# H18R1_Frontend_1.net
KiCad netlist of a schematic drawn in Altium Designer
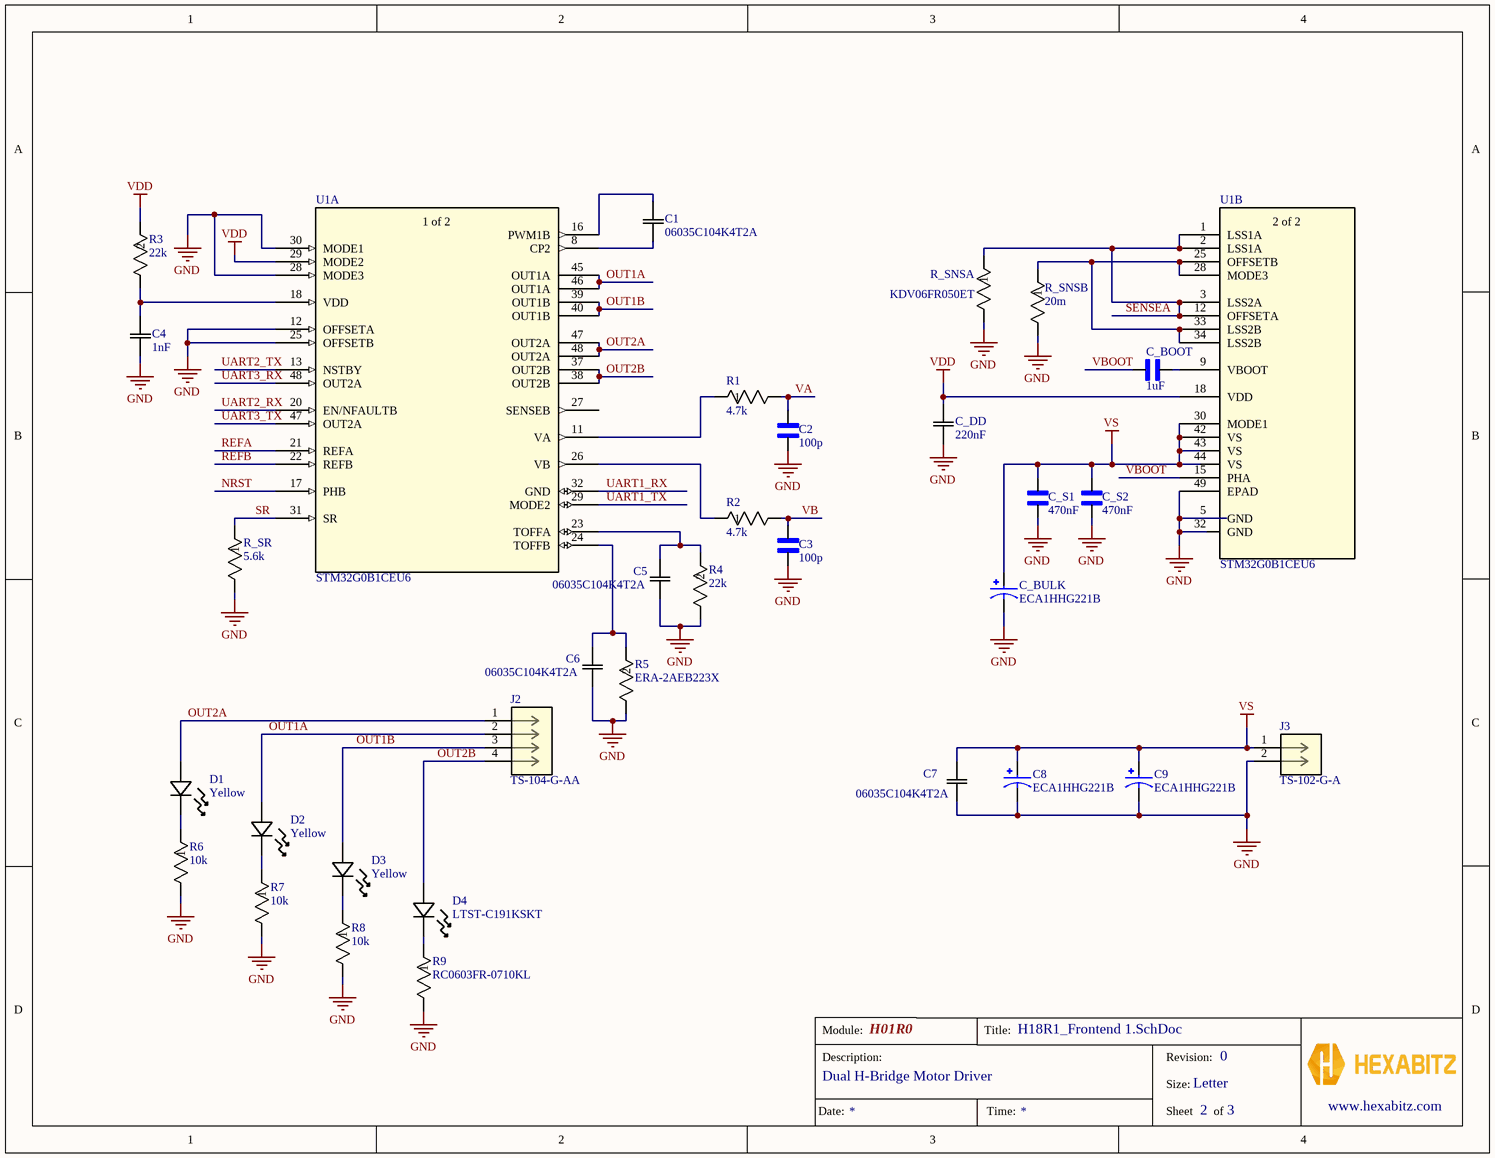
[diagram p0: H18R1_Frontend 1.SchDoc]

(export (version "E")
  (design (tool "Eeschema 10.0.6"))
  (components
    (comp (ref "C1")
      (value "06035C104K4T2A")
      (footprint "CAP_0603_AVX")
      (description "Description")
      (fields (field (name "COPYRIGHT") "Copyright (C) 2025 Ultra Librarian. All rights reserved."))
      (libsource (lib "H18R1") (part "06035C104K4T2A"))
    )
    (comp (ref "C2")
      (value "100p")
      (footprint "CAPC1005X55N")
      (description "100 pF Â±5% 50V Ceramic Capacitor C0G, NP0 0402 (1005 Metric)")
      (fields (field (name "MF") "Yageo") (field (name "MP") "CC0402JRNPO9BN101"))
      (libsource (lib "H18R1") (part "CC0402JRNPO9BN101"))
    )
    (comp (ref "C3")
      (value "100p")
      (footprint "CAPC1005X55N")
      (description "100 pF Â±5% 50V Ceramic Capacitor C0G, NP0 0402 (1005 Metric)")
      (fields (field (name "MF") "Yageo") (field (name "MP") "CC0402JRNPO9BN101"))
      (libsource (lib "H18R1") (part "CC0402JRNPO9BN101"))
    )
    (comp (ref "C4")
      (value "1nF")
      (footprint "CAPC17595_87N_KEM")
      (description "SMD Comm X7R, Ceramic, 1000 pF, 10%, 50 VDC, X7R, SMD, MLCC, Temperature Stable, Class II, 0603")
      (fields
        (field (name "MANUFACTURER_PART_NUMBER") "C0603C102K5RACTU")
        (field (name "COPYRIGHT") "Copyright (C) 2025 Ultra Librarian. All rights reserved.")
      )
      (libsource (lib "H18R1") (part "C0603C102K5RACTU"))
    )
    (comp (ref "C5")
      (value "06035C104K4T2A")
      (footprint "CAP_0603_AVX")
      (description "Description")
      (fields (field (name "COPYRIGHT") "Copyright (C) 2025 Ultra Librarian. All rights reserved."))
      (libsource (lib "H18R1") (part "06035C104K4T2A"))
    )
    (comp (ref "C6")
      (value "06035C104K4T2A")
      (footprint "CAP_0603_AVX")
      (description "Description")
      (fields (field (name "COPYRIGHT") "Copyright (C) 2025 Ultra Librarian. All rights reserved."))
      (libsource (lib "H18R1") (part "06035C104K4T2A"))
    )
    (comp (ref "C7")
      (value "06035C104K4T2A")
      (footprint "CAP_0603_AVX")
      (description "Description")
      (fields (field (name "COPYRIGHT") "Copyright (C) 2025 Ultra Librarian. All rights reserved."))
      (libsource (lib "H18R1") (part "06035C104K4T2A"))
    )
    (comp (ref "C8")
      (value "ECA1HHG221B")
      (footprint "CAPPRD500W60D1000H1250:CAPPRD500W60D1000H1250")
      (description "Cap Aluminum Lytic 220uF 50V 20% (10 X 12.5mm) Radial 5mm 300mA 2000h 105??? Ammo Pack")
      (fields (field (name "MF") "Panasonic Electronic") (field (name "MP") "ECA-1HHG221B"))
      (libsource (lib "H18R1") (part "ECA1HHG221B"))
    )
    (comp (ref "C9")
      (value "ECA1HHG221B")
      (footprint "CAPPRD500W60D1000H1250:CAPPRD500W60D1000H1250")
      (description "Cap Aluminum Lytic 220uF 50V 20% (10 X 12.5mm) Radial 5mm 300mA 2000h 105??? Ammo Pack")
      (fields (field (name "MF") "Panasonic Electronic") (field (name "MP") "ECA-1HHG221B"))
      (libsource (lib "ECA1HHG221B") (part "ECA1HHG221B"))
    )
    (comp (ref "C_BOOT")
      (value "1uF")
      (footprint "CAPC2012X135N")
      (description "1 ÂµF Â±10% 50V Ceramic Capacitor X7R 0805 (2012 Metric)")
      (fields (field (name "MF") "Samsung") (field (name "MP") "CL21B105KBFNNNE"))
      (libsource (lib "H18R1") (part "CL21B105KBFNNNE"))
    )
    (comp (ref "C_BULK")
      (value "ECA1HHG221B")
      (footprint "CAPPRD500W60D1000H1250:CAPPRD500W60D1000H1250")
      (description "Cap Aluminum Lytic 220uF 50V 20% (10 X 12.5mm) Radial 5mm 300mA 2000h 105??? Ammo Pack")
      (fields (field (name "MF") "Panasonic Electronic") (field (name "MP") "ECA-1HHG221B"))
      (libsource (lib "ECA1HHG221B") (part "ECA1HHG221B"))
    )
    (comp (ref "C_DD")
      (value "220nF")
      (footprint "cap_UMK105 CG080CV-F_TAY")
      (description "Description")
      (fields
        (field (name "MANUFACTURER_PART_NUMBER") "UMK105BJ224KV-F")
        (field (name "COPYRIGHT") "Copyright (C) 2025 Ultra Librarian. All rights reserved.")
      )
      (libsource (lib "H18R1") (part "UMK105BJ224KV-F"))
    )
    (comp (ref "C_S1")
      (value "470nF")
      (footprint "CAPC1005X60N")
      (description "SMD capacitor X5R(EIA) with capacitance 0.47uF Tol.10%. Rated voltage 50Vdc 85C")
      (fields (field (name "MF") "Murata Electronics") (field (name "MP") "GRM155R61H474KE11D"))
      (libsource (lib "H18R1") (part "GRM155R61H474KE11D"))
    )
    (comp (ref "C_S2")
      (value "470nF")
      (footprint "CAPC1005X60N")
      (description "SMD capacitor X5R(EIA) with capacitance 0.47uF Tol.10%. Rated voltage 50Vdc 85C")
      (fields (field (name "MF") "Murata Electronics") (field (name "MP") "GRM155R61H474KE11D"))
      (libsource (lib "H18R1") (part "GRM155R61H474KE11D"))
    )
    (comp (ref "D1")
      (value "Yellow")
      (footprint "LED_LTST-C191KRKT_LTO")
      (description "Description")
      (fields
        (field (name "MANUFACTURER_PART_NUMBER") "LTST-C191KSKT")
        (field (name "COPYRIGHT") "Copyright (C) 2025 Ultra Librarian. All rights reserved.")
      )
      (libsource (lib "H18R1") (part "LTST-C191KSKT"))
    )
    (comp (ref "D2")
      (value "Yellow")
      (footprint "LED_LTST-C191KRKT_LTO")
      (description "Description")
      (fields
        (field (name "MANUFACTURER_PART_NUMBER") "LTST-C191KSKT")
        (field (name "COPYRIGHT") "Copyright (C) 2025 Ultra Librarian. All rights reserved.")
      )
      (libsource (lib "H18R1") (part "LTST-C191KSKT"))
    )
    (comp (ref "D3")
      (value "Yellow")
      (footprint "LED_LTST-C191KRKT_LTO")
      (description "Description")
      (fields
        (field (name "MANUFACTURER_PART_NUMBER") "LTST-C191KSKT")
        (field (name "COPYRIGHT") "Copyright (C) 2025 Ultra Librarian. All rights reserved.")
      )
      (libsource (lib "H18R1") (part "LTST-C191KSKT"))
    )
    (comp (ref "D4")
      (value "LTST-C191KSKT")
      (footprint "LED_LTST-C191KRKT_LTO")
      (description "Description")
      (fields (field (name "COPYRIGHT") "Copyright (C) 2025 Ultra Librarian. All rights reserved."))
      (libsource (lib "H18R1") (part "LTST-C191KSKT"))
    )
    (comp (ref "J2")
      (value "TS-104-G-AA")
      (footprint "CON4_1X4_TU_HTS_SAI")
      (description "Description")
      (fields (field (name "COPYRIGHT") "Copyright (C) 2025 Ultra Librarian. All rights reserved."))
      (libsource (lib "H18R1") (part "TS-104-G-AA"))
    )
    (comp (ref "J3")
      (value "TS-102-G-A")
      (footprint "CON2_1X2_TU_HTS_SAI")
      (description "Description")
      (fields (field (name "COPYRIGHT") "Copyright (C) 2025 Ultra Librarian. All rights reserved."))
      (libsource (lib "H18R1") (part "TS-102-G-A"))
    )
    (comp (ref "R1")
      (value "4.7k")
      (footprint "YAG_R0402_YAG")
      (description "Description")
      (fields
        (field (name "MANUFACTURER_PART_NUMBER") "RC0402FR-074K7L")
        (field (name "COPYRIGHT") "Copyright (C) 2025 Ultra Librarian. All rights reserved.")
      )
      (libsource (lib "H18R1") (part "RC0402FR-074K7L"))
    )
    (comp (ref "R2")
      (value "4.7k")
      (footprint "YAG_R0402_YAG")
      (description "Description")
      (fields
        (field (name "MANUFACTURER_PART_NUMBER") "RC0402FR-074K7L")
        (field (name "COPYRIGHT") "Copyright (C) 2025 Ultra Librarian. All rights reserved.")
      )
      (libsource (lib "H18R1") (part "RC0402FR-074K7L"))
    )
    (comp (ref "R3")
      (value "22k")
      (footprint "RC0402N_PAN")
      (description "Description")
      (fields
        (field (name "MANUFACTURER_PART_NUMBER") "ERA-2AEB223X")
        (field (name "COPYRIGHT") "Copyright (C) 2025 Ultra Librarian. All rights reserved.")
      )
      (libsource (lib "H18R1") (part "ERA-2AEB223X"))
    )
    (comp (ref "R4")
      (value "22k")
      (footprint "RC0402N_PAN")
      (description "Description")
      (fields
        (field (name "MANUFACTURER_PART_NUMBER") "ERA-2AEB223X")
        (field (name "COPYRIGHT") "Copyright (C) 2025 Ultra Librarian. All rights reserved.")
      )
      (libsource (lib "H18R1") (part "ERA-2AEB223X"))
    )
    (comp (ref "R5")
      (value "ERA-2AEB223X")
      (footprint "RC0402N_PAN")
      (description "Description")
      (fields (field (name "COPYRIGHT") "Copyright (C) 2025 Ultra Librarian. All rights reserved."))
      (libsource (lib "H18R1") (part "ERA-2AEB223X"))
    )
    (comp (ref "R6")
      (value "10k")
      (footprint "RC0603N_YAG")
      (description "RES SMD 10kO 1% 1/10W 0603")
      (fields
        (field (name "MANUFACTURER_PART_NUMBER") "RC0603FR-0710KL")
        (field (name "COPYRIGHT") "Copyright (C) 2025 Ultra Librarian. All rights reserved.")
      )
      (libsource (lib "H18R1") (part "RC0603FR-0710KL"))
    )
    (comp (ref "R7")
      (value "10k")
      (footprint "RC0603N_YAG")
      (description "RES SMD 10kO 1% 1/10W 0603")
      (fields
        (field (name "MANUFACTURER_PART_NUMBER") "RC0603FR-0710KL")
        (field (name "COPYRIGHT") "Copyright (C) 2025 Ultra Librarian. All rights reserved.")
      )
      (libsource (lib "H18R1") (part "RC0603FR-0710KL"))
    )
    (comp (ref "R8")
      (value "10k")
      (footprint "RC0603N_YAG")
      (description "RES SMD 10kO 1% 1/10W 0603")
      (fields
        (field (name "MANUFACTURER_PART_NUMBER") "RC0603FR-0710KL")
        (field (name "COPYRIGHT") "Copyright (C) 2025 Ultra Librarian. All rights reserved.")
      )
      (libsource (lib "H18R1") (part "RC0603FR-0710KL"))
    )
    (comp (ref "R9")
      (value "RC0603FR-0710KL")
      (footprint "RC0603N_YAG")
      (description "RES SMD 10kO 1% 1/10W 0603")
      (fields (field (name "COPYRIGHT") "Copyright (C) 2025 Ultra Librarian. All rights reserved."))
      (libsource (lib "H18R1") (part "RC0603FR-0710KL"))
    )
    (comp (ref "R_SNSA")
      (value "KDV06FR050ET")
      (footprint "RES_KDV06_OHM")
      (description "Description")
      (fields (field (name "COPYRIGHT") "Copyright (C) 2025 Ultra Librarian. All rights reserved."))
      (libsource (lib "H18R1") (part "KDV06FR050ET"))
    )
    (comp (ref "R_SNSB")
      (value "20m")
      (footprint "RES_KDV06_OHM")
      (description "Description")
      (fields
        (field (name "MANUFACTURER_PART_NUMBER") "KDV06FR050ET")
        (field (name "COPYRIGHT") "Copyright (C) 2025 Ultra Librarian. All rights reserved.")
      )
      (libsource (lib "H18R1") (part "KDV06FR050ET"))
    )
    (comp (ref "R_SR")
      (value "5.6k")
      (footprint "YAG_R0402_YAG")
      (description "No Description Available")
      (fields
        (field (name "MANUFACTURER_PART_NUMBER") "RC0402FR-075K6L")
        (field (name "COPYRIGHT") "Copyright (C) 2025 Ultra Librarian. All rights reserved.")
      )
      (libsource (lib "H18R1") (part "RC0402FR-075K6L"))
    )
    (comp (ref "U1")
      (value "STM32G0B1CEU6")
      (footprint "QFN50P700X700X65-49N-D")
      (description "Scalable 4.5 A dual full-bridge driver for brushed DC motors")
      (fields
        (field (name "MANUFACTURER_PART_NUMBER") "STSPIN948")
        (field (name "COPYRIGHT") "Copyright (C) 2025 Ultra Librarian. All rights reserved.")
      )
      (libsource (lib "") (part "STSPIN948_1"))
    )
  )
  (nets
    (net (code "1") (name "/NRST") (class "Default")
      (node (ref "U1") (pin "17") (pinfunction "PHB_17") (pintype "input"))
    )
    (net (code "2") (name "/OUT1A") (class "Default")
      (node (ref "D2") (pin "2") (pinfunction "2_2") (pintype "passive"))
      (node (ref "J2") (pin "2") (pinfunction "2_2") (pintype "passive"))
      (node (ref "U1") (pin "45") (pinfunction "OUT1A_45") (pintype "power_in"))
      (node (ref "U1") (pin "46") (pinfunction "OUT1A_46") (pintype "power_in"))
    )
    (net (code "3") (name "/OUT1B") (class "Default")
      (node (ref "D3") (pin "2") (pinfunction "2_2") (pintype "passive"))
      (node (ref "J2") (pin "3") (pinfunction "3_3") (pintype "passive"))
      (node (ref "U1") (pin "39") (pinfunction "OUT1B_39") (pintype "power_in"))
      (node (ref "U1") (pin "40") (pinfunction "OUT1B_40") (pintype "power_in"))
    )
    (net (code "4") (name "/OUT2A") (class "Default")
      (node (ref "D1") (pin "2") (pinfunction "2_2") (pintype "passive"))
      (node (ref "J2") (pin "1") (pinfunction "1_1") (pintype "passive"))
      (node (ref "U1") (pin "47") (pinfunction "OUT2A_47") (pintype "power_in"))
      (node (ref "U1") (pin "48") (pinfunction "OUT2A_48") (pintype "power_in"))
    )
    (net (code "5") (name "/OUT2B") (class "Default")
      (node (ref "D4") (pin "2") (pinfunction "2_2") (pintype "passive"))
      (node (ref "J2") (pin "4") (pinfunction "4_4") (pintype "passive"))
      (node (ref "U1") (pin "37") (pinfunction "OUT2B_37") (pintype "power_in"))
      (node (ref "U1") (pin "38") (pinfunction "OUT2B_38") (pintype "power_in"))
    )
    (net (code "6") (name "/REFA") (class "Default")
      (node (ref "U1") (pin "21") (pinfunction "REFA_21") (pintype "input"))
    )
    (net (code "7") (name "/REFB") (class "Default")
      (node (ref "U1") (pin "22") (pinfunction "REFB_22") (pintype "input"))
    )
    (net (code "8") (name "/SENSEA") (class "Default")
      (node (ref "R_SNSA") (pin "1") (pinfunction "1_1") (pintype "passive"))
      (node (ref "U1") (pin "1") (pinfunction "LSS1A_1") (pintype "power_in"))
      (node (ref "U1") (pin "12") (pinfunction "OFFSETA_12") (pintype "power_in"))
      (node (ref "U1") (pin "2") (pinfunction "LSS1A_2") (pintype "power_in"))
      (node (ref "U1") (pin "3") (pinfunction "LSS2A_3") (pintype "power_in"))
    )
    (net (code "9") (name "/SR") (class "Default")
      (node (ref "R_SR") (pin "1") (pinfunction "1_1") (pintype "passive"))
      (node (ref "U1") (pin "31") (pinfunction "SR_31") (pintype "input"))
    )
    (net (code "10") (name "/UART1_RX") (class "Default")
      (node (ref "U1") (pin "32") (pinfunction "GND_32") (pintype "bidirectional"))
    )
    (net (code "11") (name "/UART1_TX") (class "Default")
      (node (ref "U1") (pin "29") (pinfunction "MODE2_29") (pintype "bidirectional"))
    )
    (net (code "12") (name "/UART2_RX") (class "Default")
      (node (ref "U1") (pin "20") (pinfunction "EN/NFAULTB_20") (pintype "input"))
    )
    (net (code "13") (name "/UART2_TX") (class "Default")
      (node (ref "U1") (pin "13") (pinfunction "NSTBY_13") (pintype "input"))
    )
    (net (code "14") (name "/UART3_RX") (class "Default")
      (node (ref "U1") (pin "48") (pinfunction "OUT2A_48") (pintype "input"))
    )
    (net (code "15") (name "/UART3_TX") (class "Default")
      (node (ref "U1") (pin "47") (pinfunction "OUT2A_47") (pintype "input"))
    )
    (net (code "16") (name "/VA") (class "Default")
      (node (ref "C2") (pin "1") (pinfunction "1_1") (pintype "passive"))
      (node (ref "R1") (pin "2") (pinfunction "2_2") (pintype "passive"))
    )
    (net (code "17") (name "/VB") (class "Default")
      (node (ref "C3") (pin "1") (pinfunction "1_1") (pintype "passive"))
      (node (ref "R2") (pin "2") (pinfunction "2_2") (pintype "passive"))
    )
    (net (code "18") (name "/VBOOT") (class "Default")
      (node (ref "C_BOOT") (pin "1") (pinfunction "1_1") (pintype "passive"))
      (node (ref "U1") (pin "15") (pinfunction "PHA_15") (pintype "power_in"))
    )
    (net (code "19") (name "GND") (class "Default")
      (node (ref "C2") (pin "2") (pinfunction "2_2") (pintype "passive"))
      (node (ref "C3") (pin "2") (pinfunction "2_2") (pintype "passive"))
      (node (ref "C4") (pin "2") (pinfunction "2_2") (pintype "passive"))
      (node (ref "C5") (pin "2") (pinfunction "2_2") (pintype "passive"))
      (node (ref "C6") (pin "2") (pinfunction "2_2") (pintype "passive"))
      (node (ref "C7") (pin "2") (pinfunction "2_2") (pintype "passive"))
      (node (ref "C8") (pin "N") (pinfunction "N_N") (pintype "passive"))
      (node (ref "C9") (pin "N") (pinfunction "N_N") (pintype "passive"))
      (node (ref "C_BULK") (pin "N") (pinfunction "N_N") (pintype "passive"))
      (node (ref "C_DD") (pin "2") (pinfunction "2_2") (pintype "passive"))
      (node (ref "C_S1") (pin "2") (pinfunction "2_2") (pintype "passive"))
      (node (ref "C_S2") (pin "2") (pinfunction "2_2") (pintype "passive"))
      (node (ref "J3") (pin "2") (pinfunction "2_2") (pintype "passive"))
      (node (ref "R4") (pin "1") (pinfunction "1_1") (pintype "passive"))
      (node (ref "R5") (pin "1") (pinfunction "1_1") (pintype "passive"))
      (node (ref "R6") (pin "2") (pinfunction "2_2") (pintype "passive"))
      (node (ref "R7") (pin "2") (pinfunction "2_2") (pintype "passive"))
      (node (ref "R8") (pin "2") (pinfunction "2_2") (pintype "passive"))
      (node (ref "R9") (pin "2") (pinfunction "2_2") (pintype "passive"))
      (node (ref "R_SNSA") (pin "2") (pinfunction "2_2") (pintype "passive"))
      (node (ref "R_SNSB") (pin "2") (pinfunction "2_2") (pintype "passive"))
      (node (ref "R_SR") (pin "2") (pinfunction "2_2") (pintype "passive"))
      (node (ref "U1") (pin "12") (pinfunction "OFFSETA_12") (pintype "input"))
      (node (ref "U1") (pin "25") (pinfunction "OFFSETB_25") (pintype "input"))
      (node (ref "U1") (pin "28") (pinfunction "MODE3_28") (pintype "input"))
      (node (ref "U1") (pin "30") (pinfunction "MODE1_30") (pintype "input"))
      (node (ref "U1") (pin "32") (pinfunction "GND_32") (pintype "power_in"))
      (node (ref "U1") (pin "49") (pinfunction "EPAD_49") (pintype "power_in"))
      (node (ref "U1") (pin "5") (pinfunction "GND_5") (pintype "power_in"))
    )
    (net (code "20") (name "Net-(D1-Pad1)") (class "Default")
      (node (ref "D1") (pin "1") (pinfunction "1_1") (pintype "passive"))
      (node (ref "R6") (pin "1") (pinfunction "1_1") (pintype "passive"))
    )
    (net (code "21") (name "Net-(D2-Pad1)") (class "Default")
      (node (ref "D2") (pin "1") (pinfunction "1_1") (pintype "passive"))
      (node (ref "R7") (pin "1") (pinfunction "1_1") (pintype "passive"))
    )
    (net (code "22") (name "Net-(D3-Pad1)") (class "Default")
      (node (ref "D3") (pin "1") (pinfunction "1_1") (pintype "passive"))
      (node (ref "R8") (pin "1") (pinfunction "1_1") (pintype "passive"))
    )
    (net (code "23") (name "Net-(D4-Pad1)") (class "Default")
      (node (ref "D4") (pin "1") (pinfunction "1_1") (pintype "passive"))
      (node (ref "R9") (pin "1") (pinfunction "1_1") (pintype "passive"))
    )
    (net (code "24") (name "Net-(U1A-CP2)") (class "Default")
      (node (ref "C1") (pin "2") (pinfunction "2_2") (pintype "passive"))
      (node (ref "U1") (pin "8") (pinfunction "CP2_8") (pintype "output"))
    )
    (net (code "25") (name "Net-(U1A-PWM1B)") (class "Default")
      (node (ref "C1") (pin "1") (pinfunction "1_1") (pintype "passive"))
      (node (ref "U1") (pin "16") (pinfunction "PWM1B_16") (pintype "output"))
    )
    (net (code "26") (name "Net-(U1A-TOFFA)") (class "Default")
      (node (ref "C5") (pin "1") (pinfunction "1_1") (pintype "passive"))
      (node (ref "R4") (pin "2") (pinfunction "2_2") (pintype "passive"))
      (node (ref "U1") (pin "23") (pinfunction "TOFFA_23") (pintype "bidirectional"))
    )
    (net (code "27") (name "Net-(U1A-TOFFB)") (class "Default")
      (node (ref "C6") (pin "1") (pinfunction "1_1") (pintype "passive"))
      (node (ref "R5") (pin "2") (pinfunction "2_2") (pintype "passive"))
      (node (ref "U1") (pin "24") (pinfunction "TOFFB_24") (pintype "bidirectional"))
    )
    (net (code "28") (name "Net-(U1A-VA)") (class "Default")
      (node (ref "R1") (pin "1") (pinfunction "1_1") (pintype "passive"))
      (node (ref "U1") (pin "11") (pinfunction "VA_11") (pintype "output"))
    )
    (net (code "29") (name "Net-(U1A-VB)") (class "Default")
      (node (ref "R2") (pin "1") (pinfunction "1_1") (pintype "passive"))
      (node (ref "U1") (pin "26") (pinfunction "VB_26") (pintype "output"))
    )
    (net (code "30") (name "Net-(U1A-VDD)") (class "Default")
      (node (ref "C4") (pin "1") (pinfunction "1_1") (pintype "passive"))
      (node (ref "R3") (pin "1") (pinfunction "1_1") (pintype "passive"))
      (node (ref "U1") (pin "18") (pinfunction "VDD_18") (pintype "input"))
    )
    (net (code "31") (name "Net-(U1B-MODE3)") (class "Default")
      (node (ref "R_SNSB") (pin "1") (pinfunction "1_1") (pintype "passive"))
      (node (ref "U1") (pin "25") (pinfunction "OFFSETB_25") (pintype "power_in"))
      (node (ref "U1") (pin "28") (pinfunction "MODE3_28") (pintype "power_in"))
      (node (ref "U1") (pin "33") (pinfunction "LSS2B_33") (pintype "power_in"))
      (node (ref "U1") (pin "34") (pinfunction "LSS2B_34") (pintype "power_in"))
    )
    (net (code "32") (name "Net-(U1B-VBOOT)") (class "Default")
      (node (ref "C_BOOT") (pin "2") (pinfunction "2_2") (pintype "passive"))
      (node (ref "U1") (pin "9") (pinfunction "VBOOT_9") (pintype "power_in"))
    )
    (net (code "33") (name "VDD") (class "Default")
      (node (ref "C_DD") (pin "1") (pinfunction "1_1") (pintype "passive"))
      (node (ref "R3") (pin "2") (pinfunction "2_2") (pintype "passive"))
      (node (ref "U1") (pin "18") (pinfunction "VDD_18") (pintype "power_in"))
      (node (ref "U1") (pin "29") (pinfunction "MODE2_29") (pintype "input"))
    )
    (net (code "34") (name "VS") (class "Default")
      (node (ref "C7") (pin "1") (pinfunction "1_1") (pintype "passive"))
      (node (ref "C8") (pin "P") (pinfunction "P_P") (pintype "passive"))
      (node (ref "C9") (pin "P") (pinfunction "P_P") (pintype "passive"))
      (node (ref "C_BULK") (pin "P") (pinfunction "P_P") (pintype "passive"))
      (node (ref "C_S1") (pin "1") (pinfunction "1_1") (pintype "passive"))
      (node (ref "C_S2") (pin "1") (pinfunction "1_1") (pintype "passive"))
      (node (ref "J3") (pin "1") (pinfunction "1_1") (pintype "passive"))
      (node (ref "U1") (pin "30") (pinfunction "MODE1_30") (pintype "power_in"))
      (node (ref "U1") (pin "42") (pinfunction "VS_42") (pintype "power_in"))
      (node (ref "U1") (pin "43") (pinfunction "VS_43") (pintype "power_in"))
      (node (ref "U1") (pin "44") (pinfunction "VS_44") (pintype "power_in"))
    )
    (net (code "35") (name "unconnected-(U1A-SENSEB-Pad27)") (class "Default")
      (node (ref "U1") (pin "27") (pinfunction "SENSEB_27") (pintype "output"))
    )
  )
)
